# xe-sas.net
KiCad netlist of a schematic drawn in EAGLE
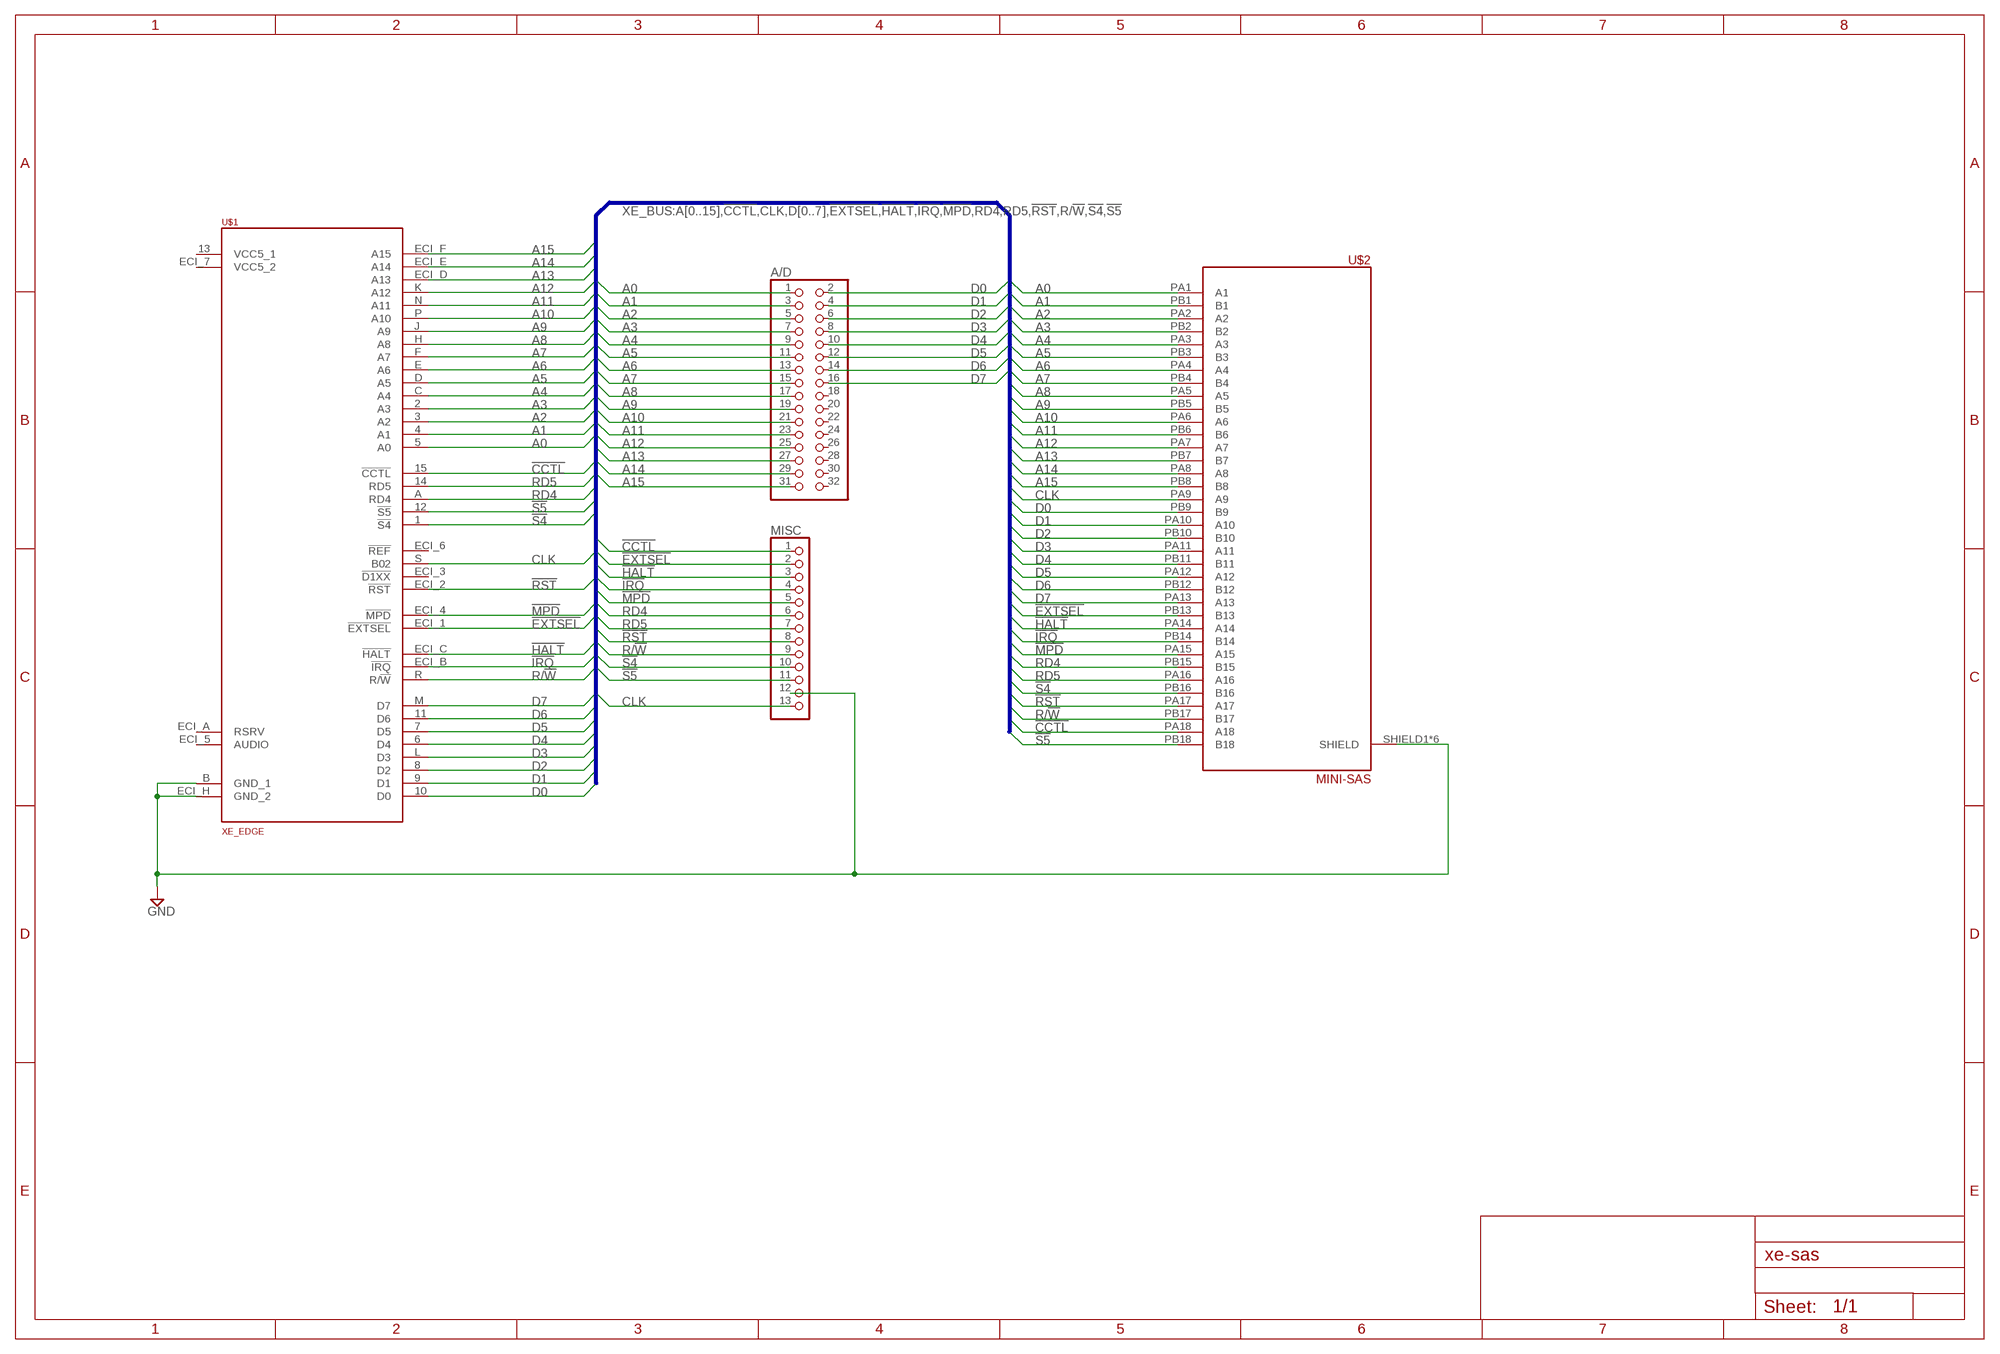
[diagram p0: schematic, sheet 1]

(export (version "E")
  (design (tool "Eeschema 10.0.6"))
  (components
    (comp (ref "A/D")
      (value "PINHD-2X16")
      (footprint "eagle-import:2X16")
      (libsource (lib "eagle-import") (part "PINHD-2X16"))
    )
    (comp (ref "MISC")
      (value "PINHD-1X13")
      (footprint "eagle-import:1X13")
      (libsource (lib "eagle-import") (part "PINHD-1X13"))
    )
    (comp (ref "U$1")
      (value "XE_EDGE")
      (footprint "eagle-import:XE_EDGE")
      (libsource (lib "eagle-import") (part "XE_EDGE"))
    )
    (comp (ref "U$2")
      (value "MINI-SAS")
      (footprint "eagle-import:MINI-SAS")
      (libsource (lib "eagle-import") (part "MINI-SAS"))
    )
  )
  (nets
    (net (code "1") (name "/A0") (class "Default")
      (node (ref "A/D") (pin "1") (pinfunction "1_1") (pintype "passive"))
      (node (ref "U$1") (pin "5") (pinfunction "A0_5") (pintype "bidirectional"))
      (node (ref "U$2") (pin "PA1") (pinfunction "A1_PA1") (pintype "bidirectional"))
    )
    (net (code "2") (name "/A1") (class "Default")
      (node (ref "A/D") (pin "3") (pinfunction "3_3") (pintype "passive"))
      (node (ref "U$1") (pin "4") (pinfunction "A1_4") (pintype "bidirectional"))
      (node (ref "U$2") (pin "PB1") (pinfunction "B1_PB1") (pintype "bidirectional"))
    )
    (net (code "3") (name "/A2") (class "Default")
      (node (ref "A/D") (pin "5") (pinfunction "5_5") (pintype "passive"))
      (node (ref "U$1") (pin "3") (pinfunction "A2_3") (pintype "bidirectional"))
      (node (ref "U$2") (pin "PA2") (pinfunction "A2_PA2") (pintype "bidirectional"))
    )
    (net (code "4") (name "/A3") (class "Default")
      (node (ref "A/D") (pin "7") (pinfunction "7_7") (pintype "passive"))
      (node (ref "U$1") (pin "2") (pinfunction "A3_2") (pintype "bidirectional"))
      (node (ref "U$2") (pin "PB2") (pinfunction "B2_PB2") (pintype "bidirectional"))
    )
    (net (code "5") (name "/A4") (class "Default")
      (node (ref "A/D") (pin "9") (pinfunction "9_9") (pintype "passive"))
      (node (ref "U$1") (pin "C") (pinfunction "A4_C") (pintype "bidirectional"))
      (node (ref "U$2") (pin "PA3") (pinfunction "A3_PA3") (pintype "bidirectional"))
    )
    (net (code "6") (name "/A5") (class "Default")
      (node (ref "A/D") (pin "11") (pinfunction "11_11") (pintype "passive"))
      (node (ref "U$1") (pin "D") (pinfunction "A5_D") (pintype "bidirectional"))
      (node (ref "U$2") (pin "PB3") (pinfunction "B3_PB3") (pintype "bidirectional"))
    )
    (net (code "7") (name "/A6") (class "Default")
      (node (ref "A/D") (pin "13") (pinfunction "13_13") (pintype "passive"))
      (node (ref "U$1") (pin "E") (pinfunction "A6_E") (pintype "bidirectional"))
      (node (ref "U$2") (pin "PA4") (pinfunction "A4_PA4") (pintype "bidirectional"))
    )
    (net (code "8") (name "/A7") (class "Default")
      (node (ref "A/D") (pin "15") (pinfunction "15_15") (pintype "passive"))
      (node (ref "U$1") (pin "F") (pinfunction "A7_F") (pintype "bidirectional"))
      (node (ref "U$2") (pin "PB4") (pinfunction "B4_PB4") (pintype "bidirectional"))
    )
    (net (code "9") (name "/A8") (class "Default")
      (node (ref "A/D") (pin "17") (pinfunction "17_17") (pintype "passive"))
      (node (ref "U$1") (pin "H") (pinfunction "A8_H") (pintype "bidirectional"))
      (node (ref "U$2") (pin "PA5") (pinfunction "A5_PA5") (pintype "bidirectional"))
    )
    (net (code "10") (name "/A9") (class "Default")
      (node (ref "A/D") (pin "19") (pinfunction "19_19") (pintype "passive"))
      (node (ref "U$1") (pin "J") (pinfunction "A9_J") (pintype "bidirectional"))
      (node (ref "U$2") (pin "PB5") (pinfunction "B5_PB5") (pintype "bidirectional"))
    )
    (net (code "11") (name "/A10") (class "Default")
      (node (ref "A/D") (pin "21") (pinfunction "21_21") (pintype "passive"))
      (node (ref "U$1") (pin "P") (pinfunction "A10_P") (pintype "bidirectional"))
      (node (ref "U$2") (pin "PA6") (pinfunction "A6_PA6") (pintype "bidirectional"))
    )
    (net (code "12") (name "/A11") (class "Default")
      (node (ref "A/D") (pin "23") (pinfunction "23_23") (pintype "passive"))
      (node (ref "U$1") (pin "N") (pinfunction "A11_N") (pintype "bidirectional"))
      (node (ref "U$2") (pin "PB6") (pinfunction "B6_PB6") (pintype "bidirectional"))
    )
    (net (code "13") (name "/A12") (class "Default")
      (node (ref "A/D") (pin "25") (pinfunction "25_25") (pintype "passive"))
      (node (ref "U$1") (pin "K") (pinfunction "A12_K") (pintype "bidirectional"))
      (node (ref "U$2") (pin "PA7") (pinfunction "A7_PA7") (pintype "bidirectional"))
    )
    (net (code "14") (name "/A13") (class "Default")
      (node (ref "A/D") (pin "27") (pinfunction "27_27") (pintype "passive"))
      (node (ref "U$1") (pin "ECI_D") (pinfunction "A13_ECI_D") (pintype "bidirectional"))
      (node (ref "U$2") (pin "PB7") (pinfunction "B7_PB7") (pintype "bidirectional"))
    )
    (net (code "15") (name "/A14") (class "Default")
      (node (ref "A/D") (pin "29") (pinfunction "29_29") (pintype "passive"))
      (node (ref "U$1") (pin "ECI_E") (pinfunction "A14_ECI_E") (pintype "bidirectional"))
      (node (ref "U$2") (pin "PA8") (pinfunction "A8_PA8") (pintype "bidirectional"))
    )
    (net (code "16") (name "/A15") (class "Default")
      (node (ref "A/D") (pin "31") (pinfunction "31_31") (pintype "passive"))
      (node (ref "U$1") (pin "ECI_F") (pinfunction "A15_ECI_F") (pintype "bidirectional"))
      (node (ref "U$2") (pin "PB8") (pinfunction "B8_PB8") (pintype "bidirectional"))
    )
    (net (code "17") (name "/CLK") (class "Default")
      (node (ref "MISC") (pin "13") (pinfunction "13_13") (pintype "passive"))
      (node (ref "U$1") (pin "S") (pinfunction "B02_S") (pintype "bidirectional"))
      (node (ref "U$2") (pin "PA9") (pinfunction "A9_PA9") (pintype "bidirectional"))
    )
    (net (code "18") (name "/D0") (class "Default")
      (node (ref "A/D") (pin "2") (pinfunction "2_2") (pintype "passive"))
      (node (ref "U$1") (pin "10") (pinfunction "D0_10") (pintype "bidirectional"))
      (node (ref "U$2") (pin "PB9") (pinfunction "B9_PB9") (pintype "bidirectional"))
    )
    (net (code "19") (name "/D1") (class "Default")
      (node (ref "A/D") (pin "4") (pinfunction "4_4") (pintype "passive"))
      (node (ref "U$1") (pin "9") (pinfunction "D1_9") (pintype "bidirectional"))
      (node (ref "U$2") (pin "PA10") (pinfunction "A10_PA10") (pintype "bidirectional"))
    )
    (net (code "20") (name "/D2") (class "Default")
      (node (ref "A/D") (pin "6") (pinfunction "6_6") (pintype "passive"))
      (node (ref "U$1") (pin "8") (pinfunction "D2_8") (pintype "bidirectional"))
      (node (ref "U$2") (pin "PB10") (pinfunction "B10_PB10") (pintype "bidirectional"))
    )
    (net (code "21") (name "/D3") (class "Default")
      (node (ref "A/D") (pin "8") (pinfunction "8_8") (pintype "passive"))
      (node (ref "U$1") (pin "L") (pinfunction "D3_L") (pintype "bidirectional"))
      (node (ref "U$2") (pin "PA11") (pinfunction "A11_PA11") (pintype "bidirectional"))
    )
    (net (code "22") (name "/D4") (class "Default")
      (node (ref "A/D") (pin "10") (pinfunction "10_10") (pintype "passive"))
      (node (ref "U$1") (pin "6") (pinfunction "D4_6") (pintype "bidirectional"))
      (node (ref "U$2") (pin "PB11") (pinfunction "B11_PB11") (pintype "bidirectional"))
    )
    (net (code "23") (name "/D5") (class "Default")
      (node (ref "A/D") (pin "12") (pinfunction "12_12") (pintype "passive"))
      (node (ref "U$1") (pin "7") (pinfunction "D5_7") (pintype "bidirectional"))
      (node (ref "U$2") (pin "PA12") (pinfunction "A12_PA12") (pintype "bidirectional"))
    )
    (net (code "24") (name "/D6") (class "Default")
      (node (ref "A/D") (pin "14") (pinfunction "14_14") (pintype "passive"))
      (node (ref "U$1") (pin "11") (pinfunction "D6_11") (pintype "bidirectional"))
      (node (ref "U$2") (pin "PB12") (pinfunction "B12_PB12") (pintype "bidirectional"))
    )
    (net (code "25") (name "/D7") (class "Default")
      (node (ref "A/D") (pin "16") (pinfunction "16_16") (pintype "passive"))
      (node (ref "U$1") (pin "M") (pinfunction "D7_M") (pintype "bidirectional"))
      (node (ref "U$2") (pin "PA13") (pinfunction "A13_PA13") (pintype "bidirectional"))
    )
    (net (code "26") (name "/RD4") (class "Default")
      (node (ref "MISC") (pin "6") (pinfunction "6_6") (pintype "passive"))
      (node (ref "U$1") (pin "A") (pinfunction "RD4_A") (pintype "bidirectional"))
      (node (ref "U$2") (pin "PB15") (pinfunction "B15_PB15") (pintype "bidirectional"))
    )
    (net (code "27") (name "/RD5") (class "Default")
      (node (ref "MISC") (pin "7") (pinfunction "7_7") (pintype "passive"))
      (node (ref "U$1") (pin "14") (pinfunction "RD5_14") (pintype "bidirectional"))
      (node (ref "U$2") (pin "PA16") (pinfunction "A16_PA16") (pintype "bidirectional"))
    )
    (net (code "28") (name "/R{slash}~{W}") (class "Default")
      (node (ref "MISC") (pin "9") (pinfunction "9_9") (pintype "passive"))
      (node (ref "U$1") (pin "R") (pinfunction "R/~{W}_R") (pintype "bidirectional"))
      (node (ref "U$2") (pin "PB17") (pinfunction "B17_PB17") (pintype "bidirectional"))
    )
    (net (code "30") (name "/~{CCTL}") (class "Default")
      (node (ref "MISC") (pin "1") (pinfunction "1_1") (pintype "passive"))
      (node (ref "U$1") (pin "15") (pinfunction "~{CCTL}_15") (pintype "bidirectional"))
      (node (ref "U$2") (pin "PA18") (pinfunction "A18_PA18") (pintype "bidirectional"))
    )
    (net (code "31") (name "/~{EXTSEL}") (class "Default")
      (node (ref "MISC") (pin "2") (pinfunction "2_2") (pintype "passive"))
      (node (ref "U$1") (pin "ECI_1") (pinfunction "~{EXTSEL}_ECI_1") (pintype "bidirectional"))
      (node (ref "U$2") (pin "PB13") (pinfunction "B13_PB13") (pintype "bidirectional"))
    )
    (net (code "32") (name "/~{HALT}") (class "Default")
      (node (ref "MISC") (pin "3") (pinfunction "3_3") (pintype "passive"))
      (node (ref "U$1") (pin "ECI_C") (pinfunction "~{HALT}_ECI_C") (pintype "bidirectional"))
      (node (ref "U$2") (pin "PA14") (pinfunction "A14_PA14") (pintype "bidirectional"))
    )
    (net (code "33") (name "/~{IRQ}") (class "Default")
      (node (ref "MISC") (pin "4") (pinfunction "4_4") (pintype "passive"))
      (node (ref "U$1") (pin "ECI_B") (pinfunction "~{IRQ}_ECI_B") (pintype "bidirectional"))
      (node (ref "U$2") (pin "PB14") (pinfunction "B14_PB14") (pintype "bidirectional"))
    )
    (net (code "34") (name "/~{MPD}") (class "Default")
      (node (ref "MISC") (pin "5") (pinfunction "5_5") (pintype "passive"))
      (node (ref "U$1") (pin "ECI_4") (pinfunction "~{MPD}_ECI_4") (pintype "bidirectional"))
      (node (ref "U$2") (pin "PA15") (pinfunction "A15_PA15") (pintype "bidirectional"))
    )
    (net (code "35") (name "/~{RST}") (class "Default")
      (node (ref "MISC") (pin "8") (pinfunction "8_8") (pintype "passive"))
      (node (ref "U$1") (pin "ECI_2") (pinfunction "~{RST}_ECI_2") (pintype "bidirectional"))
      (node (ref "U$2") (pin "PA17") (pinfunction "A17_PA17") (pintype "bidirectional"))
    )
    (net (code "36") (name "/~{S4}") (class "Default")
      (node (ref "MISC") (pin "10") (pinfunction "10_10") (pintype "passive"))
      (node (ref "U$1") (pin "1") (pinfunction "~{S4}_1") (pintype "bidirectional"))
      (node (ref "U$2") (pin "PB16") (pinfunction "B16_PB16") (pintype "bidirectional"))
    )
    (net (code "37") (name "/~{S5}") (class "Default")
      (node (ref "MISC") (pin "11") (pinfunction "11_11") (pintype "passive"))
      (node (ref "U$1") (pin "12") (pinfunction "~{S5}_12") (pintype "bidirectional"))
      (node (ref "U$2") (pin "PB18") (pinfunction "B18_PB18") (pintype "bidirectional"))
    )
    (net (code "38") (name "GND") (class "Default")
      (node (ref "MISC") (pin "12") (pinfunction "12_12") (pintype "passive"))
      (node (ref "U$1") (pin "B") (pinfunction "GND_1_B") (pintype "bidirectional"))
      (node (ref "U$1") (pin "ECI_H") (pinfunction "GND_2_ECI_H") (pintype "bidirectional"))
      (node (ref "U$2") (pin "SHIELD1") (pinfunction "SHIELD_SHIELD1") (pintype "bidirectional"))
      (node (ref "U$2") (pin "SHIELD2") (pinfunction "SHIELD_SHIELD2") (pintype "bidirectional"))
      (node (ref "U$2") (pin "SHIELD3") (pinfunction "SHIELD_SHIELD3") (pintype "bidirectional"))
      (node (ref "U$2") (pin "SHIELD4") (pinfunction "SHIELD_SHIELD4") (pintype "bidirectional"))
      (node (ref "U$2") (pin "SHIELD5") (pinfunction "SHIELD_SHIELD5") (pintype "bidirectional"))
      (node (ref "U$2") (pin "SHIELD6") (pinfunction "SHIELD_SHIELD6") (pintype "bidirectional"))
    )
    (net (code "39") (name "unconnected-(A/D-Pad18)") (class "Default")
      (node (ref "A/D") (pin "18") (pinfunction "18_18") (pintype "passive"))
    )
    (net (code "40") (name "unconnected-(A/D-Pad20)") (class "Default")
      (node (ref "A/D") (pin "20") (pinfunction "20_20") (pintype "passive"))
    )
    (net (code "41") (name "unconnected-(A/D-Pad22)") (class "Default")
      (node (ref "A/D") (pin "22") (pinfunction "22_22") (pintype "passive"))
    )
    (net (code "42") (name "unconnected-(A/D-Pad24)") (class "Default")
      (node (ref "A/D") (pin "24") (pinfunction "24_24") (pintype "passive"))
    )
    (net (code "43") (name "unconnected-(A/D-Pad26)") (class "Default")
      (node (ref "A/D") (pin "26") (pinfunction "26_26") (pintype "passive"))
    )
    (net (code "44") (name "unconnected-(A/D-Pad28)") (class "Default")
      (node (ref "A/D") (pin "28") (pinfunction "28_28") (pintype "passive"))
    )
    (net (code "45") (name "unconnected-(A/D-Pad30)") (class "Default")
      (node (ref "A/D") (pin "30") (pinfunction "30_30") (pintype "passive"))
    )
    (net (code "46") (name "unconnected-(A/D-Pad32)") (class "Default")
      (node (ref "A/D") (pin "32") (pinfunction "32_32") (pintype "passive"))
    )
    (net (code "47") (name "unconnected-(U$1-AUDIO-PadECI_5)") (class "Default")
      (node (ref "U$1") (pin "ECI_5") (pinfunction "AUDIO_ECI_5") (pintype "bidirectional"))
    )
    (net (code "48") (name "unconnected-(U$1-RSRV-PadECI_A)") (class "Default")
      (node (ref "U$1") (pin "ECI_A") (pinfunction "RSRV_ECI_A") (pintype "bidirectional"))
    )
    (net (code "49") (name "unconnected-(U$1-VCC5_1-Pad13)") (class "Default")
      (node (ref "U$1") (pin "13") (pinfunction "VCC5_1_13") (pintype "bidirectional"))
    )
    (net (code "50") (name "unconnected-(U$1-VCC5_2-PadECI_7)") (class "Default")
      (node (ref "U$1") (pin "ECI_7") (pinfunction "VCC5_2_ECI_7") (pintype "bidirectional"))
    )
    (net (code "51") (name "unconnected-(U$1-~{D1XX}-PadECI_3)") (class "Default")
      (node (ref "U$1") (pin "ECI_3") (pinfunction "~{D1XX}_ECI_3") (pintype "bidirectional"))
    )
    (net (code "52") (name "unconnected-(U$1-~{REF}-PadECI_6)") (class "Default")
      (node (ref "U$1") (pin "ECI_6") (pinfunction "~{REF}_ECI_6") (pintype "bidirectional"))
    )
  )
)
